# 06_Power_Supply.net
KiCad netlist of a schematic drawn in Altium Designer
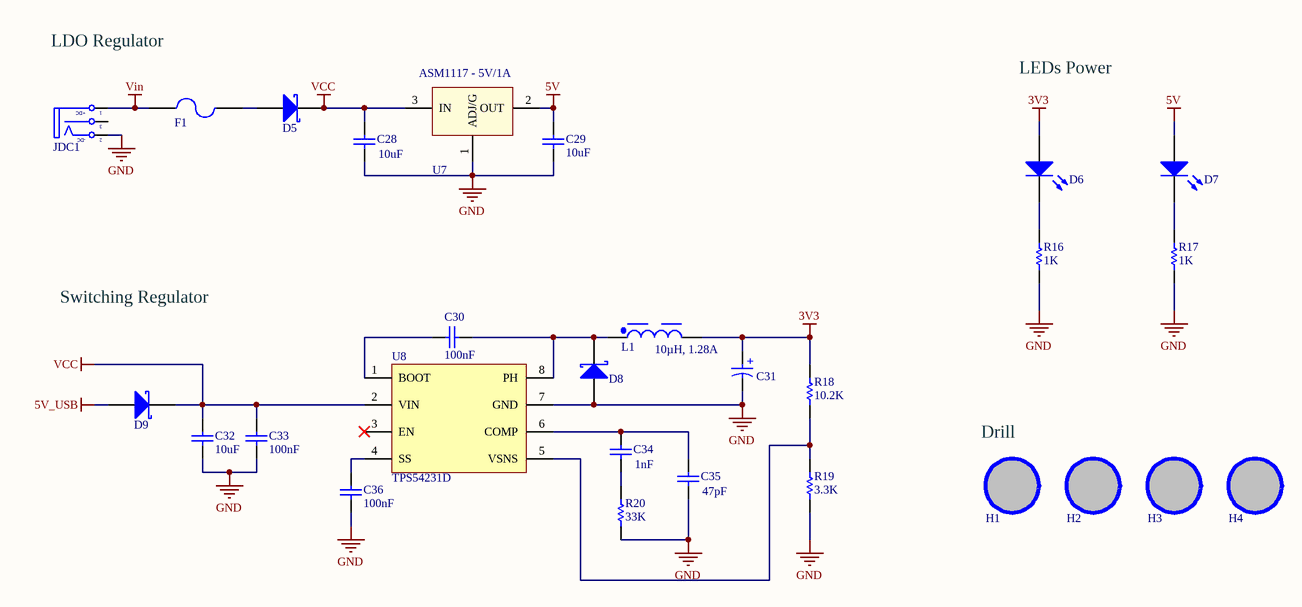
[diagram p0: 06_Power_Supply.SchDoc]

(export (version "E")
  (design (tool "Eeschema 10.0.6"))
  (components
    (comp (ref "C28")
      (value "10uF")
      (footprint "CAP-SM-0805")
      (description "Capacitor")
      (fields (field (name "Comment") "Cap Non-Pol SMD"))
      (libsource (lib "PIF_Library") (part "Cap Non-Pol SMD"))
    )
    (comp (ref "C29")
      (value "10uF")
      (footprint "CAP-SM-0805")
      (description "Capacitor")
      (fields (field (name "Comment") "Cap Non-Pol SMD"))
      (libsource (lib "PIF_Library") (part "Cap Non-Pol SMD"))
    )
    (comp (ref "C30")
      (value "100nF")
      (footprint "CAP-SM-0805")
      (description "Capacitor")
      (fields (field (name "Comment") "Cap Non-Pol SMD"))
      (libsource (lib "PIF_Library") (part "Cap Non-Pol SMD"))
    )
    (comp (ref "C31")
      (value "100uF")
      (footprint "WCAP-ASLI_D6.3H5.5")
      (description "WCAP-ASLI Aluminum Electrolytic Capacitor, V-Chip, D6.3 x H5.5mm, 100uF, 10V")
      (fields
        (field (name "MANUFACTURER PART NUMBER") "865080243007")
        (field (name "MANUFACTURER") "Wurth Elektronik")
      )
      (libsource (lib "Altium_WCAP-ASLI (rev22d)") (part "865080243007"))
    )
    (comp (ref "C32")
      (value "10uF")
      (footprint "CAP-SM-0805")
      (description "Capacitor")
      (fields (field (name "Comment") "Cap Non-Pol SMD"))
      (libsource (lib "PIF_Library") (part "Cap Non-Pol SMD"))
    )
    (comp (ref "C33")
      (value "100nF")
      (footprint "CAP-SM-0805")
      (description "Capacitor")
      (fields (field (name "Comment") "Cap Non-Pol SMD"))
      (libsource (lib "PIF_Library") (part "Cap Non-Pol SMD"))
    )
    (comp (ref "C34")
      (value "1nF")
      (footprint "CAP-SM-0805")
      (description "Capacitor")
      (fields (field (name "Comment") "Cap Non-Pol SMD"))
      (libsource (lib "PIF_Library") (part "Cap Non-Pol SMD"))
    )
    (comp (ref "C35")
      (value "47pF")
      (footprint "CAP-SM-0805")
      (description "Capacitor")
      (fields (field (name "Comment") "Cap Non-Pol SMD"))
      (libsource (lib "PIF_Library") (part "Cap Non-Pol SMD"))
    )
    (comp (ref "C36")
      (value "100nF")
      (footprint "CAP-SM-0805")
      (description "Capacitor")
      (fields (field (name "Comment") "Cap Non-Pol SMD"))
      (libsource (lib "PIF_Library") (part "Cap Non-Pol SMD"))
    )
    (comp (ref "D5")
      (value "D Schottky")
      (footprint "SS34")
      (description "Schottky Diode")
      (fields (field (name "PUBLISHER") "Altium Limited"))
      (libsource (lib "PIF_Library") (part "D Schottky"))
    )
    (comp (ref "D6")
      (value "LED SMD")
      (footprint "LED_0805_Blue")
      (description "LED")
      (libsource (lib "PIF_Library") (part "LED SMD"))
    )
    (comp (ref "D7")
      (value "LED SMD")
      (footprint "LED_0805_Blue")
      (description "LED")
      (libsource (lib "PIF_Library") (part "LED SMD"))
    )
    (comp (ref "D8")
      (value "D Schottky")
      (footprint "SS34")
      (description "Schottky Diode")
      (fields (field (name "PUBLISHER") "Altium Limited"))
      (libsource (lib "PIF_Library") (part "D Schottky"))
    )
    (comp (ref "D9")
      (value "D Schottky")
      (footprint "SS34")
      (description "Schottky Diode")
      (fields (field (name "PUBLISHER") "Altium Limited"))
      (libsource (lib "PIF_Library") (part "D Schottky"))
    )
    (comp (ref "F1") (value "Fuse") (footprint "FUSE SMD") (libsource (lib "PIF_Library") (part "Fuse")))
    (comp (ref "H1")
      (value "Hole")
      (footprint "LO KHOAN 3MM")
      (description "Hole 3mm")
      (libsource (lib "PIF_Library") (part "Hole"))
    )
    (comp (ref "H2")
      (value "Hole")
      (footprint "LO KHOAN 3MM")
      (description "Hole 3mm")
      (libsource (lib "PIF_Library") (part "Hole"))
    )
    (comp (ref "H3")
      (value "Hole")
      (footprint "LO KHOAN 3MM")
      (description "Hole 3mm")
      (libsource (lib "PIF_Library") (part "Hole"))
    )
    (comp (ref "H4")
      (value "Hole")
      (footprint "LO KHOAN 3MM")
      (description "Hole 3mm")
      (libsource (lib "PIF_Library") (part "Hole"))
    )
    (comp (ref "JDC1")
      (value "Jack DC")
      (footprint "DC-IN")
      (description "Jack DC input")
      (libsource (lib "PIF_Library") (part "Jack DC"))
    )
    (comp (ref "L1")
      (value "10µH, 1.28A")
      (footprint "WE-PD2_3521")
      (description "WE-PD2 SMT Power Inductor, size 3521, 10µH, 0.8A, 0.3Ω")
      (fields
        (field (name "MANUFACTURER PART NUMBER") "7447732110")
        (field (name "MANUFACTURER") "Wurth Elektronik")
      )
      (libsource (lib "WE-PD2 (rev22d)") (part "7447732110"))
    )
    (comp (ref "R16")
      (value "1K")
      (footprint "RES-SM-0805")
      (description "Resistor")
      (fields (field (name "Comment") "RESISTOR SMD"))
      (libsource (lib "PIF_Library") (part "RESISTOR SMD"))
    )
    (comp (ref "R17")
      (value "1K")
      (footprint "RES-SM-0805")
      (description "Resistor")
      (fields (field (name "Comment") "RESISTOR SMD"))
      (libsource (lib "PIF_Library") (part "RESISTOR SMD"))
    )
    (comp (ref "R18")
      (value "10.2K")
      (footprint "RES-SM-0805")
      (description "Resistor")
      (fields (field (name "Comment") "RESISTOR SMD"))
      (libsource (lib "PIF_Library") (part "RESISTOR SMD"))
    )
    (comp (ref "R19")
      (value "3.3K")
      (footprint "RES-SM-0805")
      (description "Resistor")
      (fields (field (name "Comment") "RESISTOR SMD"))
      (libsource (lib "PIF_Library") (part "RESISTOR SMD"))
    )
    (comp (ref "R20")
      (value "33K")
      (footprint "RES-SM-0805")
      (description "Resistor")
      (fields (field (name "Comment") "RESISTOR SMD"))
      (libsource (lib "PIF_Library") (part "RESISTOR SMD"))
    )
    (comp (ref "U7")
      (value "ASM1117 - 5V/1A")
      (footprint "SOT223-4N")
      (description "Available in 1.8V, 2.5V, 2.85V, 3.3V, 5V, and  Adjustable Versions")
      (libsource (lib "PIF_Library") (part "LM1117"))
    )
    (comp (ref "U8")
      (value "TPS54231D")
      (footprint "SOIC8")
      (description "Buck Switching Regulator IC Positive Adjustable 0.8V 1 Output 2A 8-SOIC (0.154\", 3.90mm Width)")
      (fields (field (name "MFR") "Texas Instruments"))
      (libsource (lib "YenDoo") (part "TPS54231"))
    )
  )
  (nets
    (net (code "1") (name "3V3") (class "Default")
      (node (ref "C31") (pin "1") (pinfunction "P_1") (pintype "passive"))
      (node (ref "D6") (pin "1") (pinfunction "A_1") (pintype "passive"))
      (node (ref "L1") (pin "2") (pinfunction "2_2") (pintype "passive"))
      (node (ref "R18") (pin "2") (pinfunction "2_2") (pintype "passive"))
    )
    (net (code "2") (name "5V") (class "Default")
      (node (ref "C29") (pin "2") (pinfunction "2_2") (pintype "passive"))
      (node (ref "D7") (pin "1") (pinfunction "A_1") (pintype "passive"))
      (node (ref "U7") (pin "2") (pinfunction "OUT_2") (pintype "passive"))
    )
    (net (code "3") (name "5V_USB") (class "Default")
      (node (ref "D9") (pin "1") (pinfunction "A_1") (pintype "passive"))
    )
    (net (code "4") (name "GND") (class "Default")
      (node (ref "C28") (pin "1") (pinfunction "1_1") (pintype "passive"))
      (node (ref "C29") (pin "1") (pinfunction "1_1") (pintype "passive"))
      (node (ref "C31") (pin "2") (pinfunction "N_2") (pintype "passive"))
      (node (ref "C32") (pin "1") (pinfunction "1_1") (pintype "passive"))
      (node (ref "C33") (pin "1") (pinfunction "1_1") (pintype "passive"))
      (node (ref "C35") (pin "1") (pinfunction "1_1") (pintype "passive"))
      (node (ref "C36") (pin "1") (pinfunction "1_1") (pintype "passive"))
      (node (ref "D8") (pin "1") (pinfunction "A_1") (pintype "passive"))
      (node (ref "JDC1") (pin "2") (pinfunction "TN_2") (pintype "passive"))
      (node (ref "R16") (pin "1") (pinfunction "1_1") (pintype "passive"))
      (node (ref "R17") (pin "1") (pinfunction "1_1") (pintype "passive"))
      (node (ref "R19") (pin "1") (pinfunction "1_1") (pintype "passive"))
      (node (ref "R20") (pin "1") (pinfunction "1_1") (pintype "passive"))
      (node (ref "U7") (pin "1") (pinfunction "ADJ/G_1") (pintype "passive"))
      (node (ref "U8") (pin "7") (pinfunction "GND_7") (pintype "passive"))
    )
    (net (code "5") (name "Net-(C34-Pad1)") (class "Default")
      (node (ref "C34") (pin "1") (pinfunction "1_1") (pintype "passive"))
      (node (ref "R20") (pin "2") (pinfunction "2_2") (pintype "passive"))
    )
    (net (code "6") (name "Net-(D5-A)") (class "Default")
      (node (ref "D5") (pin "1") (pinfunction "A_1") (pintype "passive"))
      (node (ref "F1") (pin "2") (pinfunction "2_2") (pintype "passive"))
    )
    (net (code "7") (name "Net-(D6-K)") (class "Default")
      (node (ref "D6") (pin "2") (pinfunction "K_2") (pintype "passive"))
      (node (ref "R16") (pin "2") (pinfunction "2_2") (pintype "passive"))
    )
    (net (code "8") (name "Net-(D7-K)") (class "Default")
      (node (ref "D7") (pin "2") (pinfunction "K_2") (pintype "passive"))
      (node (ref "R17") (pin "2") (pinfunction "2_2") (pintype "passive"))
    )
    (net (code "9") (name "Net-(D8-K)") (class "Default")
      (node (ref "C30") (pin "1") (pinfunction "1_1") (pintype "passive"))
      (node (ref "D8") (pin "2") (pinfunction "K_2") (pintype "passive"))
      (node (ref "L1") (pin "1") (pinfunction "1_1") (pintype "passive"))
      (node (ref "U8") (pin "8") (pinfunction "PH_8") (pintype "passive"))
    )
    (net (code "10") (name "Net-(U8-BOOT)") (class "Default")
      (node (ref "C30") (pin "2") (pinfunction "2_2") (pintype "passive"))
      (node (ref "U8") (pin "1") (pinfunction "BOOT_1") (pintype "passive"))
    )
    (net (code "11") (name "Net-(U8-COMP)") (class "Default")
      (node (ref "C34") (pin "2") (pinfunction "2_2") (pintype "passive"))
      (node (ref "C35") (pin "2") (pinfunction "2_2") (pintype "passive"))
      (node (ref "U8") (pin "6") (pinfunction "COMP_6") (pintype "passive"))
    )
    (net (code "12") (name "Net-(U8-SS)") (class "Default")
      (node (ref "C36") (pin "2") (pinfunction "2_2") (pintype "passive"))
      (node (ref "U8") (pin "4") (pinfunction "SS_4") (pintype "passive"))
    )
    (net (code "13") (name "Net-(U8-VSNS)") (class "Default")
      (node (ref "R18") (pin "1") (pinfunction "1_1") (pintype "passive"))
      (node (ref "R19") (pin "2") (pinfunction "2_2") (pintype "passive"))
      (node (ref "U8") (pin "5") (pinfunction "VSNS_5") (pintype "passive"))
    )
    (net (code "14") (name "VCC") (class "Default")
      (node (ref "C28") (pin "2") (pinfunction "2_2") (pintype "passive"))
      (node (ref "C32") (pin "2") (pinfunction "2_2") (pintype "passive"))
      (node (ref "C33") (pin "2") (pinfunction "2_2") (pintype "passive"))
      (node (ref "D5") (pin "2") (pinfunction "K_2") (pintype "passive"))
      (node (ref "D9") (pin "2") (pinfunction "K_2") (pintype "passive"))
      (node (ref "U7") (pin "3") (pinfunction "IN_3") (pintype "passive"))
      (node (ref "U8") (pin "2") (pinfunction "VIN_2") (pintype "passive"))
    )
    (net (code "15") (name "Vin") (class "Default")
      (node (ref "F1") (pin "1") (pinfunction "1_1") (pintype "passive"))
      (node (ref "JDC1") (pin "1") (pinfunction "T_1") (pintype "passive"))
    )
    (net (code "16") (name "unconnected-(H1-Pad1)") (class "Default")
      (node (ref "H1") (pin "1") (pinfunction "1_1") (pintype "passive"))
    )
    (net (code "17") (name "unconnected-(H2-Pad1)") (class "Default")
      (node (ref "H2") (pin "1") (pinfunction "1_1") (pintype "passive"))
    )
    (net (code "18") (name "unconnected-(H3-Pad1)") (class "Default")
      (node (ref "H3") (pin "1") (pinfunction "1_1") (pintype "passive"))
    )
    (net (code "19") (name "unconnected-(H4-Pad1)") (class "Default")
      (node (ref "H4") (pin "1") (pinfunction "1_1") (pintype "passive"))
    )
    (net (code "20") (name "unconnected-(JDC1-S-Pad3)") (class "Default")
      (node (ref "JDC1") (pin "3") (pinfunction "S_3") (pintype "power_in"))
    )
    (net (code "21") (name "unconnected-(U8-EN-Pad3)") (class "Default")
      (node (ref "U8") (pin "3") (pinfunction "EN_3") (pintype "passive+no_connect"))
    )
  )
)
